# SCH_Lightbar-Sym_2024-08-25.net
KiCad netlist of a schematic drawn in EasyEDA
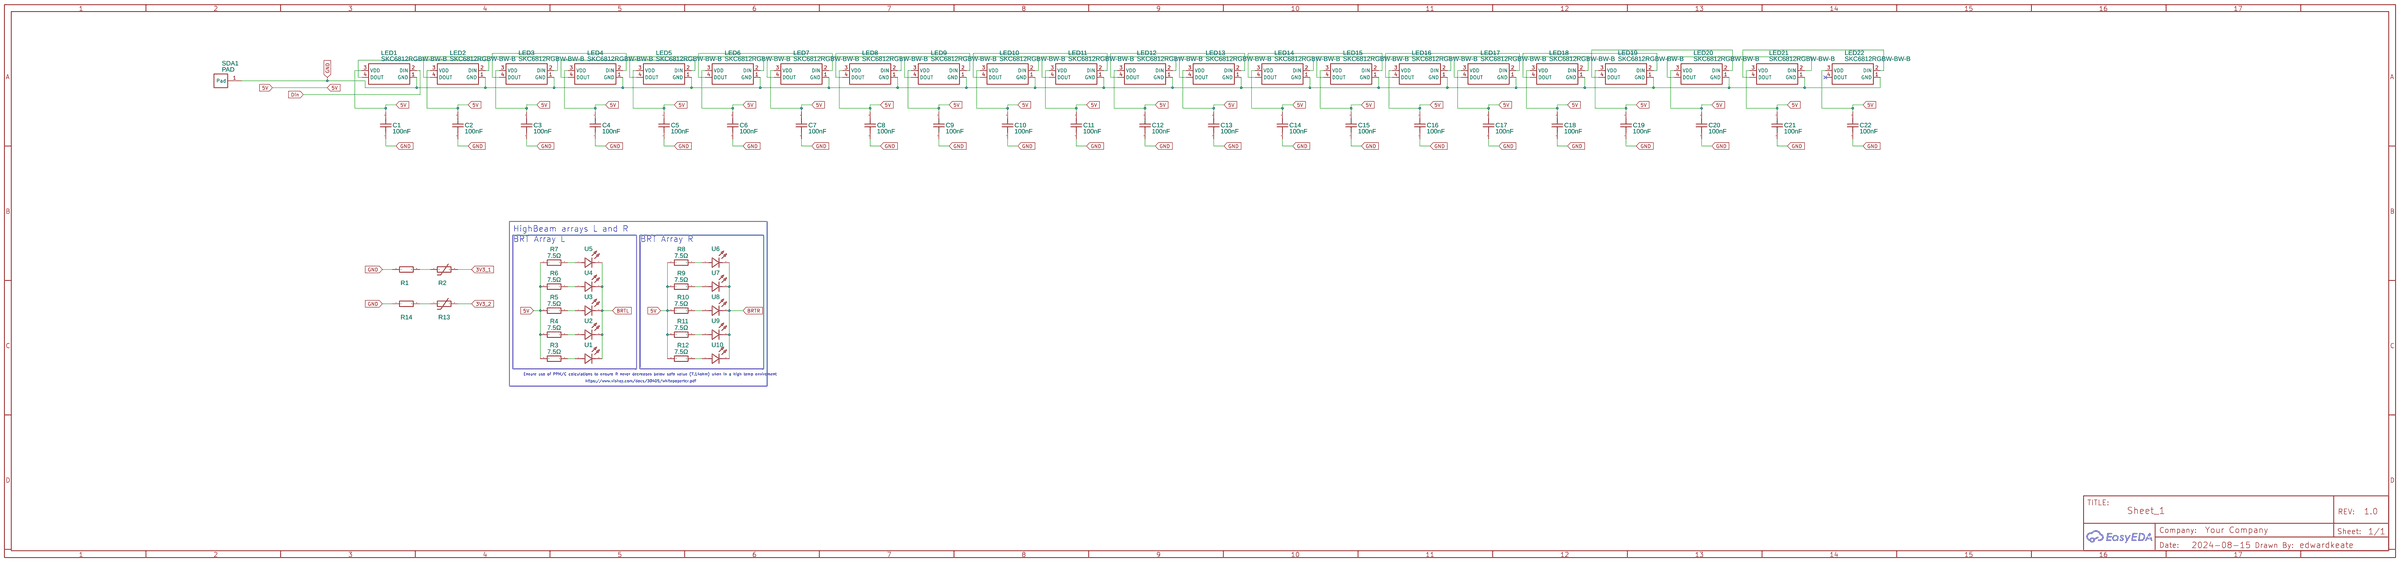
[diagram p0: schematic sheet]

(export (version "E")
  (design (tool "Eeschema 10.0.6"))
  (components
    (comp (ref "C1")
      (value "100nF")
      (fields
        (field (name "Manufacturer Part") "CC0402KRX7R6BB104")
        (field (name "Manufacturer") "YAGEO(国巨)")
      )
      (libsource (lib "") (part "CC0402KRX7R6BB104"))
    )
    (comp (ref "C2")
      (value "100nF")
      (fields
        (field (name "Manufacturer Part") "CC0402KRX7R6BB104")
        (field (name "Manufacturer") "YAGEO(国巨)")
      )
      (libsource (lib "") (part "CC0402KRX7R6BB104"))
    )
    (comp (ref "C3")
      (value "100nF")
      (fields
        (field (name "Manufacturer Part") "CC0402KRX7R6BB104")
        (field (name "Manufacturer") "YAGEO(国巨)")
      )
      (libsource (lib "") (part "CC0402KRX7R6BB104"))
    )
    (comp (ref "C4")
      (value "100nF")
      (fields
        (field (name "Manufacturer Part") "CC0402KRX7R6BB104")
        (field (name "Manufacturer") "YAGEO(国巨)")
      )
      (libsource (lib "") (part "CC0402KRX7R6BB104"))
    )
    (comp (ref "C5")
      (value "100nF")
      (fields
        (field (name "Manufacturer Part") "CC0402KRX7R6BB104")
        (field (name "Manufacturer") "YAGEO(国巨)")
      )
      (libsource (lib "") (part "CC0402KRX7R6BB104"))
    )
    (comp (ref "C6")
      (value "100nF")
      (fields
        (field (name "Manufacturer Part") "CC0402KRX7R6BB104")
        (field (name "Manufacturer") "YAGEO(国巨)")
      )
      (libsource (lib "") (part "CC0402KRX7R6BB104"))
    )
    (comp (ref "C7")
      (value "100nF")
      (fields
        (field (name "Manufacturer Part") "CC0402KRX7R6BB104")
        (field (name "Manufacturer") "YAGEO(国巨)")
      )
      (libsource (lib "") (part "CC0402KRX7R6BB104"))
    )
    (comp (ref "C8")
      (value "100nF")
      (fields
        (field (name "Manufacturer Part") "CC0402KRX7R6BB104")
        (field (name "Manufacturer") "YAGEO(国巨)")
      )
      (libsource (lib "") (part "CC0402KRX7R6BB104"))
    )
    (comp (ref "C9")
      (value "100nF")
      (fields
        (field (name "Manufacturer Part") "CC0402KRX7R6BB104")
        (field (name "Manufacturer") "YAGEO(国巨)")
      )
      (libsource (lib "") (part "CC0402KRX7R6BB104"))
    )
    (comp (ref "C10")
      (value "100nF")
      (fields
        (field (name "Manufacturer Part") "CC0402KRX7R6BB104")
        (field (name "Manufacturer") "YAGEO(国巨)")
      )
      (libsource (lib "") (part "CC0402KRX7R6BB104"))
    )
    (comp (ref "C11")
      (value "100nF")
      (fields
        (field (name "Manufacturer Part") "CC0402KRX7R6BB104")
        (field (name "Manufacturer") "YAGEO(国巨)")
      )
      (libsource (lib "") (part "CC0402KRX7R6BB104"))
    )
    (comp (ref "C12")
      (value "100nF")
      (fields
        (field (name "Manufacturer Part") "CC0402KRX7R6BB104")
        (field (name "Manufacturer") "YAGEO(国巨)")
      )
      (libsource (lib "") (part "CC0402KRX7R6BB104"))
    )
    (comp (ref "C13")
      (value "100nF")
      (fields
        (field (name "Manufacturer Part") "CC0402KRX7R6BB104")
        (field (name "Manufacturer") "YAGEO(国巨)")
      )
      (libsource (lib "") (part "CC0402KRX7R6BB104"))
    )
    (comp (ref "C14")
      (value "100nF")
      (fields
        (field (name "Manufacturer Part") "CC0402KRX7R6BB104")
        (field (name "Manufacturer") "YAGEO(国巨)")
      )
      (libsource (lib "") (part "CC0402KRX7R6BB104"))
    )
    (comp (ref "C15")
      (value "100nF")
      (fields
        (field (name "Manufacturer Part") "CC0402KRX7R6BB104")
        (field (name "Manufacturer") "YAGEO(国巨)")
      )
      (libsource (lib "") (part "CC0402KRX7R6BB104"))
    )
    (comp (ref "C16")
      (value "100nF")
      (fields
        (field (name "Manufacturer Part") "CC0402KRX7R6BB104")
        (field (name "Manufacturer") "YAGEO(国巨)")
      )
      (libsource (lib "") (part "CC0402KRX7R6BB104"))
    )
    (comp (ref "C17")
      (value "100nF")
      (fields
        (field (name "Manufacturer Part") "CC0402KRX7R6BB104")
        (field (name "Manufacturer") "YAGEO(国巨)")
      )
      (libsource (lib "") (part "CC0402KRX7R6BB104"))
    )
    (comp (ref "C18")
      (value "100nF")
      (fields
        (field (name "Manufacturer Part") "CC0402KRX7R6BB104")
        (field (name "Manufacturer") "YAGEO(国巨)")
      )
      (libsource (lib "") (part "CC0402KRX7R6BB104"))
    )
    (comp (ref "C19")
      (value "100nF")
      (fields
        (field (name "Manufacturer Part") "CC0402KRX7R6BB104")
        (field (name "Manufacturer") "YAGEO(国巨)")
      )
      (libsource (lib "") (part "CC0402KRX7R6BB104"))
    )
    (comp (ref "C20")
      (value "100nF")
      (fields
        (field (name "Manufacturer Part") "CC0402KRX7R6BB104")
        (field (name "Manufacturer") "YAGEO(国巨)")
      )
      (libsource (lib "") (part "CC0402KRX7R6BB104"))
    )
    (comp (ref "C21")
      (value "100nF")
      (fields
        (field (name "Manufacturer Part") "CC0402KRX7R6BB104")
        (field (name "Manufacturer") "YAGEO(国巨)")
      )
      (libsource (lib "") (part "CC0402KRX7R6BB104"))
    )
    (comp (ref "C22")
      (value "100nF")
      (fields
        (field (name "Manufacturer Part") "CC0402KRX7R6BB104")
        (field (name "Manufacturer") "YAGEO(国巨)")
      )
      (libsource (lib "") (part "CC0402KRX7R6BB104"))
    )
    (comp (ref "LED1")
      (value "SKC6812RGBW-BW-B")
      (fields (field (name "Manufacturer") "欧思科光电"))
      (libsource (lib "") (part "SKC6812RGBW-BW-B"))
    )
    (comp (ref "LED2")
      (value "SKC6812RGBW-BW-B")
      (fields (field (name "Manufacturer") "欧思科光电"))
      (libsource (lib "") (part "SKC6812RGBW-BW-B"))
    )
    (comp (ref "LED3")
      (value "SKC6812RGBW-BW-B")
      (fields (field (name "Manufacturer") "欧思科光电"))
      (libsource (lib "") (part "SKC6812RGBW-BW-B"))
    )
    (comp (ref "LED4")
      (value "SKC6812RGBW-BW-B")
      (fields (field (name "Manufacturer") "欧思科光电"))
      (libsource (lib "") (part "SKC6812RGBW-BW-B"))
    )
    (comp (ref "LED5")
      (value "SKC6812RGBW-BW-B")
      (fields (field (name "Manufacturer") "欧思科光电"))
      (libsource (lib "") (part "SKC6812RGBW-BW-B"))
    )
    (comp (ref "LED6")
      (value "SKC6812RGBW-BW-B")
      (fields (field (name "Manufacturer") "欧思科光电"))
      (libsource (lib "") (part "SKC6812RGBW-BW-B"))
    )
    (comp (ref "LED7")
      (value "SKC6812RGBW-BW-B")
      (fields (field (name "Manufacturer") "欧思科光电"))
      (libsource (lib "") (part "SKC6812RGBW-BW-B"))
    )
    (comp (ref "LED8")
      (value "SKC6812RGBW-BW-B")
      (fields (field (name "Manufacturer") "欧思科光电"))
      (libsource (lib "") (part "SKC6812RGBW-BW-B"))
    )
    (comp (ref "LED9")
      (value "SKC6812RGBW-BW-B")
      (fields (field (name "Manufacturer") "欧思科光电"))
      (libsource (lib "") (part "SKC6812RGBW-BW-B"))
    )
    (comp (ref "LED10")
      (value "SKC6812RGBW-BW-B")
      (fields (field (name "Manufacturer") "欧思科光电"))
      (libsource (lib "") (part "SKC6812RGBW-BW-B"))
    )
    (comp (ref "LED11")
      (value "SKC6812RGBW-BW-B")
      (fields (field (name "Manufacturer") "欧思科光电"))
      (libsource (lib "") (part "SKC6812RGBW-BW-B"))
    )
    (comp (ref "LED12")
      (value "SKC6812RGBW-BW-B")
      (fields (field (name "Manufacturer") "欧思科光电"))
      (libsource (lib "") (part "SKC6812RGBW-BW-B"))
    )
    (comp (ref "LED13")
      (value "SKC6812RGBW-BW-B")
      (fields (field (name "Manufacturer") "欧思科光电"))
      (libsource (lib "") (part "SKC6812RGBW-BW-B"))
    )
    (comp (ref "LED14")
      (value "SKC6812RGBW-BW-B")
      (fields (field (name "Manufacturer") "欧思科光电"))
      (libsource (lib "") (part "SKC6812RGBW-BW-B"))
    )
    (comp (ref "LED15")
      (value "SKC6812RGBW-BW-B")
      (fields (field (name "Manufacturer") "欧思科光电"))
      (libsource (lib "") (part "SKC6812RGBW-BW-B"))
    )
    (comp (ref "LED16")
      (value "SKC6812RGBW-BW-B")
      (fields (field (name "Manufacturer") "欧思科光电"))
      (libsource (lib "") (part "SKC6812RGBW-BW-B"))
    )
    (comp (ref "LED17")
      (value "SKC6812RGBW-BW-B")
      (fields (field (name "Manufacturer") "欧思科光电"))
      (libsource (lib "") (part "SKC6812RGBW-BW-B"))
    )
    (comp (ref "LED18")
      (value "SKC6812RGBW-BW-B")
      (fields (field (name "Manufacturer") "欧思科光电"))
      (libsource (lib "") (part "SKC6812RGBW-BW-B"))
    )
    (comp (ref "LED19")
      (value "SKC6812RGBW-BW-B")
      (fields (field (name "Manufacturer") "欧思科光电"))
      (libsource (lib "") (part "SKC6812RGBW-BW-B"))
    )
    (comp (ref "LED20")
      (value "SKC6812RGBW-BW-B")
      (fields (field (name "Manufacturer") "欧思科光电"))
      (libsource (lib "") (part "SKC6812RGBW-BW-B"))
    )
    (comp (ref "LED21")
      (value "SKC6812RGBW-BW-B")
      (fields (field (name "Manufacturer") "欧思科光电"))
      (libsource (lib "") (part "SKC6812RGBW-BW-B"))
    )
    (comp (ref "LED22")
      (value "SKC6812RGBW-BW-B")
      (fields (field (name "Manufacturer") "欧思科光电"))
      (libsource (lib "") (part "SKC6812RGBW-BW-B"))
    )
    (comp (ref "R1")
      (value "100kΩ")
      (fields
        (field (name "Manufacturer Part") "0603WAF1003T5E")
        (field (name "Manufacturer") "UNI-ROYAL(厚声)")
      )
      (libsource (lib "") (part "0603WAF1003T5E"))
    )
    (comp (ref "R2")
      (value "SDNT1608X104F3950FTF")
      (fields (field (name "Manufacturer") "Sunlord(顺络)"))
      (libsource (lib "") (part "SDNT1608X104F3950FTF"))
    )
    (comp (ref "R3")
      (value "7.5Ω")
      (fields
        (field (name "Manufacturer Part") "25121WF750KT4E")
        (field (name "Manufacturer") "UNI-ROYAL(厚声)")
      )
      (libsource (lib "") (part "25121WF750KT4E"))
    )
    (comp (ref "R4")
      (value "7.5Ω")
      (fields
        (field (name "Manufacturer Part") "25121WF750KT4E")
        (field (name "Manufacturer") "UNI-ROYAL(厚声)")
      )
      (libsource (lib "") (part "25121WF750KT4E"))
    )
    (comp (ref "R5")
      (value "7.5Ω")
      (fields
        (field (name "Manufacturer Part") "25121WF750KT4E")
        (field (name "Manufacturer") "UNI-ROYAL(厚声)")
      )
      (libsource (lib "") (part "25121WF750KT4E"))
    )
    (comp (ref "R6")
      (value "7.5Ω")
      (fields
        (field (name "Manufacturer Part") "25121WF750KT4E")
        (field (name "Manufacturer") "UNI-ROYAL(厚声)")
      )
      (libsource (lib "") (part "25121WF750KT4E"))
    )
    (comp (ref "R7")
      (value "7.5Ω")
      (fields
        (field (name "Manufacturer Part") "25121WF750KT4E")
        (field (name "Manufacturer") "UNI-ROYAL(厚声)")
      )
      (libsource (lib "") (part "25121WF750KT4E"))
    )
    (comp (ref "R8")
      (value "7.5Ω")
      (fields
        (field (name "Manufacturer Part") "25121WF750KT4E")
        (field (name "Manufacturer") "UNI-ROYAL(厚声)")
      )
      (libsource (lib "") (part "25121WF750KT4E"))
    )
    (comp (ref "R9")
      (value "7.5Ω")
      (fields
        (field (name "Manufacturer Part") "25121WF750KT4E")
        (field (name "Manufacturer") "UNI-ROYAL(厚声)")
      )
      (libsource (lib "") (part "25121WF750KT4E"))
    )
    (comp (ref "R10")
      (value "7.5Ω")
      (fields
        (field (name "Manufacturer Part") "25121WF750KT4E")
        (field (name "Manufacturer") "UNI-ROYAL(厚声)")
      )
      (libsource (lib "") (part "25121WF750KT4E"))
    )
    (comp (ref "R11")
      (value "7.5Ω")
      (fields
        (field (name "Manufacturer Part") "25121WF750KT4E")
        (field (name "Manufacturer") "UNI-ROYAL(厚声)")
      )
      (libsource (lib "") (part "25121WF750KT4E"))
    )
    (comp (ref "R12")
      (value "7.5Ω")
      (fields
        (field (name "Manufacturer Part") "25121WF750KT4E")
        (field (name "Manufacturer") "UNI-ROYAL(厚声)")
      )
      (libsource (lib "") (part "25121WF750KT4E"))
    )
    (comp (ref "R13")
      (value "SDNT1608X104F3950FTF")
      (fields (field (name "Manufacturer") "Sunlord(顺络)"))
      (libsource (lib "") (part "SDNT1608X104F3950FTF"))
    )
    (comp (ref "R14")
      (value "100kΩ")
      (fields
        (field (name "Manufacturer Part") "0603WAF1003T5E")
        (field (name "Manufacturer") "UNI-ROYAL(厚声)")
      )
      (libsource (lib "") (part "0603WAF1003T5E"))
    )
    (comp (ref "SDA1") (value "PAD") (libsource (lib "") (part "PAD")))
    (comp (ref "U1")
      (value "JNJ-LTJH0111W60/26MIL/8000-9000K")
      (fields
        (field (name "Manufacturer Part") "JNJ-LTJH0111W60/26mil/8000-9000K")
        (field (name "Manufacturer") "JNJ OPTOELECTRONICS(强生光电)")
      )
      (libsource (lib "") (part "JNJ-LTJH0111W60/26MIL/8000-9000K"))
    )
    (comp (ref "U2")
      (value "JNJ-LTJH0111W60/26MIL/8000-9000K")
      (fields
        (field (name "Manufacturer Part") "JNJ-LTJH0111W60/26mil/8000-9000K")
        (field (name "Manufacturer") "JNJ OPTOELECTRONICS(强生光电)")
      )
      (libsource (lib "") (part "JNJ-LTJH0111W60/26MIL/8000-9000K"))
    )
    (comp (ref "U3")
      (value "JNJ-LTJH0111W60/26MIL/8000-9000K")
      (fields
        (field (name "Manufacturer Part") "JNJ-LTJH0111W60/26mil/8000-9000K")
        (field (name "Manufacturer") "JNJ OPTOELECTRONICS(强生光电)")
      )
      (libsource (lib "") (part "JNJ-LTJH0111W60/26MIL/8000-9000K"))
    )
    (comp (ref "U4")
      (value "JNJ-LTJH0111W60/26MIL/8000-9000K")
      (fields
        (field (name "Manufacturer Part") "JNJ-LTJH0111W60/26mil/8000-9000K")
        (field (name "Manufacturer") "JNJ OPTOELECTRONICS(强生光电)")
      )
      (libsource (lib "") (part "JNJ-LTJH0111W60/26MIL/8000-9000K"))
    )
    (comp (ref "U5")
      (value "JNJ-LTJH0111W60/26MIL/8000-9000K")
      (fields
        (field (name "Manufacturer Part") "JNJ-LTJH0111W60/26mil/8000-9000K")
        (field (name "Manufacturer") "JNJ OPTOELECTRONICS(强生光电)")
      )
      (libsource (lib "") (part "JNJ-LTJH0111W60/26MIL/8000-9000K"))
    )
    (comp (ref "U6")
      (value "JNJ-LTJH0111W60/26MIL/8000-9000K")
      (fields
        (field (name "Manufacturer Part") "JNJ-LTJH0111W60/26mil/8000-9000K")
        (field (name "Manufacturer") "JNJ OPTOELECTRONICS(强生光电)")
      )
      (libsource (lib "") (part "JNJ-LTJH0111W60/26MIL/8000-9000K"))
    )
    (comp (ref "U7")
      (value "JNJ-LTJH0111W60/26MIL/8000-9000K")
      (fields
        (field (name "Manufacturer Part") "JNJ-LTJH0111W60/26mil/8000-9000K")
        (field (name "Manufacturer") "JNJ OPTOELECTRONICS(强生光电)")
      )
      (libsource (lib "") (part "JNJ-LTJH0111W60/26MIL/8000-9000K"))
    )
    (comp (ref "U8")
      (value "JNJ-LTJH0111W60/26MIL/8000-9000K")
      (fields
        (field (name "Manufacturer Part") "JNJ-LTJH0111W60/26mil/8000-9000K")
        (field (name "Manufacturer") "JNJ OPTOELECTRONICS(强生光电)")
      )
      (libsource (lib "") (part "JNJ-LTJH0111W60/26MIL/8000-9000K"))
    )
    (comp (ref "U9")
      (value "JNJ-LTJH0111W60/26MIL/8000-9000K")
      (fields
        (field (name "Manufacturer Part") "JNJ-LTJH0111W60/26mil/8000-9000K")
        (field (name "Manufacturer") "JNJ OPTOELECTRONICS(强生光电)")
      )
      (libsource (lib "") (part "JNJ-LTJH0111W60/26MIL/8000-9000K"))
    )
    (comp (ref "U10")
      (value "JNJ-LTJH0111W60/26MIL/8000-9000K")
      (fields
        (field (name "Manufacturer Part") "JNJ-LTJH0111W60/26mil/8000-9000K")
        (field (name "Manufacturer") "JNJ OPTOELECTRONICS(强生光电)")
      )
      (libsource (lib "") (part "JNJ-LTJH0111W60/26MIL/8000-9000K"))
    )
  )
  (nets
    (net (code "1") (name "3V3_1") (class "Default")
      (node (ref "R2") (pin "2") (pinfunction "2_2") (pintype "unspecified"))
    )
    (net (code "2") (name "3V3_2") (class "Default")
      (node (ref "R13") (pin "2") (pinfunction "2_2") (pintype "unspecified"))
    )
    (net (code "3") (name "5V") (class "Default")
      (node (ref "C1") (pin "2") (pinfunction "2_2") (pintype "unspecified"))
      (node (ref "C10") (pin "2") (pinfunction "2_2") (pintype "unspecified"))
      (node (ref "C11") (pin "2") (pinfunction "2_2") (pintype "unspecified"))
      (node (ref "C12") (pin "2") (pinfunction "2_2") (pintype "unspecified"))
      (node (ref "C13") (pin "2") (pinfunction "2_2") (pintype "unspecified"))
      (node (ref "C14") (pin "2") (pinfunction "2_2") (pintype "unspecified"))
      (node (ref "C15") (pin "2") (pinfunction "2_2") (pintype "unspecified"))
      (node (ref "C16") (pin "2") (pinfunction "2_2") (pintype "unspecified"))
      (node (ref "C17") (pin "2") (pinfunction "2_2") (pintype "unspecified"))
      (node (ref "C18") (pin "2") (pinfunction "2_2") (pintype "unspecified"))
      (node (ref "C19") (pin "2") (pinfunction "2_2") (pintype "unspecified"))
      (node (ref "C2") (pin "2") (pinfunction "2_2") (pintype "unspecified"))
      (node (ref "C20") (pin "2") (pinfunction "2_2") (pintype "unspecified"))
      (node (ref "C21") (pin "2") (pinfunction "2_2") (pintype "unspecified"))
      (node (ref "C22") (pin "2") (pinfunction "2_2") (pintype "unspecified"))
      (node (ref "C3") (pin "2") (pinfunction "2_2") (pintype "unspecified"))
      (node (ref "C4") (pin "2") (pinfunction "2_2") (pintype "unspecified"))
      (node (ref "C5") (pin "2") (pinfunction "2_2") (pintype "unspecified"))
      (node (ref "C6") (pin "2") (pinfunction "2_2") (pintype "unspecified"))
      (node (ref "C7") (pin "2") (pinfunction "2_2") (pintype "unspecified"))
      (node (ref "C8") (pin "2") (pinfunction "2_2") (pintype "unspecified"))
      (node (ref "C9") (pin "2") (pinfunction "2_2") (pintype "unspecified"))
      (node (ref "LED1") (pin "3") (pinfunction "VDD_3") (pintype "unspecified"))
      (node (ref "LED10") (pin "3") (pinfunction "VDD_3") (pintype "unspecified"))
      (node (ref "LED11") (pin "3") (pinfunction "VDD_3") (pintype "unspecified"))
      (node (ref "LED12") (pin "3") (pinfunction "VDD_3") (pintype "unspecified"))
      (node (ref "LED13") (pin "3") (pinfunction "VDD_3") (pintype "unspecified"))
      (node (ref "LED14") (pin "3") (pinfunction "VDD_3") (pintype "unspecified"))
      (node (ref "LED15") (pin "3") (pinfunction "VDD_3") (pintype "unspecified"))
      (node (ref "LED16") (pin "3") (pinfunction "VDD_3") (pintype "unspecified"))
      (node (ref "LED17") (pin "3") (pinfunction "VDD_3") (pintype "unspecified"))
      (node (ref "LED18") (pin "3") (pinfunction "VDD_3") (pintype "unspecified"))
      (node (ref "LED19") (pin "3") (pinfunction "VDD_3") (pintype "unspecified"))
      (node (ref "LED2") (pin "3") (pinfunction "VDD_3") (pintype "unspecified"))
      (node (ref "LED20") (pin "3") (pinfunction "VDD_3") (pintype "unspecified"))
      (node (ref "LED21") (pin "3") (pinfunction "VDD_3") (pintype "unspecified"))
      (node (ref "LED22") (pin "3") (pinfunction "VDD_3") (pintype "unspecified"))
      (node (ref "LED3") (pin "3") (pinfunction "VDD_3") (pintype "unspecified"))
      (node (ref "LED4") (pin "3") (pinfunction "VDD_3") (pintype "unspecified"))
      (node (ref "LED5") (pin "3") (pinfunction "VDD_3") (pintype "unspecified"))
      (node (ref "LED6") (pin "3") (pinfunction "VDD_3") (pintype "unspecified"))
      (node (ref "LED7") (pin "3") (pinfunction "VDD_3") (pintype "unspecified"))
      (node (ref "LED8") (pin "3") (pinfunction "VDD_3") (pintype "unspecified"))
      (node (ref "LED9") (pin "3") (pinfunction "VDD_3") (pintype "unspecified"))
      (node (ref "R10") (pin "1") (pinfunction "1_1") (pintype "input"))
      (node (ref "R11") (pin "1") (pinfunction "1_1") (pintype "input"))
      (node (ref "R12") (pin "1") (pinfunction "1_1") (pintype "input"))
      (node (ref "R3") (pin "1") (pinfunction "1_1") (pintype "input"))
      (node (ref "R4") (pin "1") (pinfunction "1_1") (pintype "input"))
      (node (ref "R5") (pin "1") (pinfunction "1_1") (pintype "input"))
      (node (ref "R6") (pin "1") (pinfunction "1_1") (pintype "input"))
      (node (ref "R7") (pin "1") (pinfunction "1_1") (pintype "input"))
      (node (ref "R8") (pin "1") (pinfunction "1_1") (pintype "input"))
      (node (ref "R9") (pin "1") (pinfunction "1_1") (pintype "input"))
    )
    (net (code "4") (name "BRTL") (class "Default")
      (node (ref "U1") (pin "2") (pinfunction "K_2") (pintype "unspecified"))
      (node (ref "U2") (pin "2") (pinfunction "K_2") (pintype "unspecified"))
      (node (ref "U3") (pin "2") (pinfunction "K_2") (pintype "unspecified"))
      (node (ref "U4") (pin "2") (pinfunction "K_2") (pintype "unspecified"))
      (node (ref "U5") (pin "2") (pinfunction "K_2") (pintype "unspecified"))
    )
    (net (code "5") (name "BRTR") (class "Default")
      (node (ref "U10") (pin "2") (pinfunction "K_2") (pintype "unspecified"))
      (node (ref "U6") (pin "2") (pinfunction "K_2") (pintype "unspecified"))
      (node (ref "U7") (pin "2") (pinfunction "K_2") (pintype "unspecified"))
      (node (ref "U8") (pin "2") (pinfunction "K_2") (pintype "unspecified"))
      (node (ref "U9") (pin "2") (pinfunction "K_2") (pintype "unspecified"))
    )
    (net (code "6") (name "Din") (class "Default")
      (node (ref "LED1") (pin "2") (pinfunction "DIN_2") (pintype "unspecified"))
    )
    (net (code "7") (name "GND") (class "Default")
      (node (ref "C1") (pin "1") (pinfunction "1_1") (pintype "unspecified"))
      (node (ref "C10") (pin "1") (pinfunction "1_1") (pintype "unspecified"))
      (node (ref "C11") (pin "1") (pinfunction "1_1") (pintype "unspecified"))
      (node (ref "C12") (pin "1") (pinfunction "1_1") (pintype "unspecified"))
      (node (ref "C13") (pin "1") (pinfunction "1_1") (pintype "unspecified"))
      (node (ref "C14") (pin "1") (pinfunction "1_1") (pintype "unspecified"))
      (node (ref "C15") (pin "1") (pinfunction "1_1") (pintype "unspecified"))
      (node (ref "C16") (pin "1") (pinfunction "1_1") (pintype "unspecified"))
      (node (ref "C17") (pin "1") (pinfunction "1_1") (pintype "unspecified"))
      (node (ref "C18") (pin "1") (pinfunction "1_1") (pintype "unspecified"))
      (node (ref "C19") (pin "1") (pinfunction "1_1") (pintype "unspecified"))
      (node (ref "C2") (pin "1") (pinfunction "1_1") (pintype "unspecified"))
      (node (ref "C20") (pin "1") (pinfunction "1_1") (pintype "unspecified"))
      (node (ref "C21") (pin "1") (pinfunction "1_1") (pintype "unspecified"))
      (node (ref "C22") (pin "1") (pinfunction "1_1") (pintype "unspecified"))
      (node (ref "C3") (pin "1") (pinfunction "1_1") (pintype "unspecified"))
      (node (ref "C4") (pin "1") (pinfunction "1_1") (pintype "unspecified"))
      (node (ref "C5") (pin "1") (pinfunction "1_1") (pintype "unspecified"))
      (node (ref "C6") (pin "1") (pinfunction "1_1") (pintype "unspecified"))
      (node (ref "C7") (pin "1") (pinfunction "1_1") (pintype "unspecified"))
      (node (ref "C8") (pin "1") (pinfunction "1_1") (pintype "unspecified"))
      (node (ref "C9") (pin "1") (pinfunction "1_1") (pintype "unspecified"))
      (node (ref "LED1") (pin "1") (pinfunction "GND_1") (pintype "unspecified"))
      (node (ref "LED10") (pin "1") (pinfunction "GND_1") (pintype "unspecified"))
      (node (ref "LED11") (pin "1") (pinfunction "GND_1") (pintype "unspecified"))
      (node (ref "LED12") (pin "1") (pinfunction "GND_1") (pintype "unspecified"))
      (node (ref "LED13") (pin "1") (pinfunction "GND_1") (pintype "unspecified"))
      (node (ref "LED14") (pin "1") (pinfunction "GND_1") (pintype "unspecified"))
      (node (ref "LED15") (pin "1") (pinfunction "GND_1") (pintype "unspecified"))
      (node (ref "LED16") (pin "1") (pinfunction "GND_1") (pintype "unspecified"))
      (node (ref "LED17") (pin "1") (pinfunction "GND_1") (pintype "unspecified"))
      (node (ref "LED18") (pin "1") (pinfunction "GND_1") (pintype "unspecified"))
      (node (ref "LED19") (pin "1") (pinfunction "GND_1") (pintype "unspecified"))
      (node (ref "LED2") (pin "1") (pinfunction "GND_1") (pintype "unspecified"))
      (node (ref "LED20") (pin "1") (pinfunction "GND_1") (pintype "unspecified"))
      (node (ref "LED21") (pin "1") (pinfunction "GND_1") (pintype "unspecified"))
      (node (ref "LED22") (pin "1") (pinfunction "GND_1") (pintype "unspecified"))
      (node (ref "LED3") (pin "1") (pinfunction "GND_1") (pintype "unspecified"))
      (node (ref "LED4") (pin "1") (pinfunction "GND_1") (pintype "unspecified"))
      (node (ref "LED5") (pin "1") (pinfunction "GND_1") (pintype "unspecified"))
      (node (ref "LED6") (pin "1") (pinfunction "GND_1") (pintype "unspecified"))
      (node (ref "LED7") (pin "1") (pinfunction "GND_1") (pintype "unspecified"))
      (node (ref "LED8") (pin "1") (pinfunction "GND_1") (pintype "unspecified"))
      (node (ref "LED9") (pin "1") (pinfunction "GND_1") (pintype "unspecified"))
      (node (ref "R1") (pin "1") (pinfunction "1_1") (pintype "input"))
      (node (ref "R14") (pin "1") (pinfunction "1_1") (pintype "input"))
      (node (ref "SDA1") (pin "1") (pinfunction "Pad_1") (pintype "unspecified"))
    )
    (net (code "8") (name "Net-(LED1-DOUT)") (class "Default")
      (node (ref "LED1") (pin "4") (pinfunction "DOUT_4") (pintype "unspecified"))
      (node (ref "LED2") (pin "2") (pinfunction "DIN_2") (pintype "unspecified"))
    )
    (net (code "9") (name "Net-(LED2-DOUT)") (class "Default")
      (node (ref "LED2") (pin "4") (pinfunction "DOUT_4") (pintype "unspecified"))
      (node (ref "LED3") (pin "2") (pinfunction "DIN_2") (pintype "unspecified"))
    )
    (net (code "10") (name "Net-(LED3-DOUT)") (class "Default")
      (node (ref "LED3") (pin "4") (pinfunction "DOUT_4") (pintype "unspecified"))
      (node (ref "LED4") (pin "2") (pinfunction "DIN_2") (pintype "unspecified"))
    )
    (net (code "11") (name "Net-(LED4-DOUT)") (class "Default")
      (node (ref "LED4") (pin "4") (pinfunction "DOUT_4") (pintype "unspecified"))
      (node (ref "LED5") (pin "2") (pinfunction "DIN_2") (pintype "unspecified"))
    )
    (net (code "12") (name "Net-(LED5-DOUT)") (class "Default")
      (node (ref "LED5") (pin "4") (pinfunction "DOUT_4") (pintype "unspecified"))
      (node (ref "LED6") (pin "2") (pinfunction "DIN_2") (pintype "unspecified"))
    )
    (net (code "13") (name "Net-(LED6-DOUT)") (class "Default")
      (node (ref "LED6") (pin "4") (pinfunction "DOUT_4") (pintype "unspecified"))
      (node (ref "LED7") (pin "2") (pinfunction "DIN_2") (pintype "unspecified"))
    )
    (net (code "14") (name "Net-(LED7-DOUT)") (class "Default")
      (node (ref "LED7") (pin "4") (pinfunction "DOUT_4") (pintype "unspecified"))
      (node (ref "LED8") (pin "2") (pinfunction "DIN_2") (pintype "unspecified"))
    )
    (net (code "15") (name "Net-(LED8-DOUT)") (class "Default")
      (node (ref "LED8") (pin "4") (pinfunction "DOUT_4") (pintype "unspecified"))
      (node (ref "LED9") (pin "2") (pinfunction "DIN_2") (pintype "unspecified"))
    )
    (net (code "16") (name "Net-(LED10-DIN)") (class "Default")
      (node (ref "LED10") (pin "2") (pinfunction "DIN_2") (pintype "unspecified"))
      (node (ref "LED9") (pin "4") (pinfunction "DOUT_4") (pintype "unspecified"))
    )
    (net (code "17") (name "Net-(LED10-DOUT)") (class "Default")
      (node (ref "LED10") (pin "4") (pinfunction "DOUT_4") (pintype "unspecified"))
      (node (ref "LED11") (pin "2") (pinfunction "DIN_2") (pintype "unspecified"))
    )
    (net (code "18") (name "Net-(LED11-DOUT)") (class "Default")
      (node (ref "LED11") (pin "4") (pinfunction "DOUT_4") (pintype "unspecified"))
      (node (ref "LED12") (pin "2") (pinfunction "DIN_2") (pintype "unspecified"))
    )
    (net (code "19") (name "Net-(LED12-DOUT)") (class "Default")
      (node (ref "LED12") (pin "4") (pinfunction "DOUT_4") (pintype "unspecified"))
      (node (ref "LED13") (pin "2") (pinfunction "DIN_2") (pintype "unspecified"))
    )
    (net (code "20") (name "Net-(LED13-DOUT)") (class "Default")
      (node (ref "LED13") (pin "4") (pinfunction "DOUT_4") (pintype "unspecified"))
      (node (ref "LED14") (pin "2") (pinfunction "DIN_2") (pintype "unspecified"))
    )
    (net (code "21") (name "Net-(LED14-DOUT)") (class "Default")
      (node (ref "LED14") (pin "4") (pinfunction "DOUT_4") (pintype "unspecified"))
      (node (ref "LED15") (pin "2") (pinfunction "DIN_2") (pintype "unspecified"))
    )
    (net (code "22") (name "Net-(LED15-DOUT)") (class "Default")
      (node (ref "LED15") (pin "4") (pinfunction "DOUT_4") (pintype "unspecified"))
      (node (ref "LED16") (pin "2") (pinfunction "DIN_2") (pintype "unspecified"))
    )
    (net (code "23") (name "Net-(LED16-DOUT)") (class "Default")
      (node (ref "LED16") (pin "4") (pinfunction "DOUT_4") (pintype "unspecified"))
      (node (ref "LED17") (pin "2") (pinfunction "DIN_2") (pintype "unspecified"))
    )
    (net (code "24") (name "Net-(LED17-DOUT)") (class "Default")
      (node (ref "LED17") (pin "4") (pinfunction "DOUT_4") (pintype "unspecified"))
      (node (ref "LED18") (pin "2") (pinfunction "DIN_2") (pintype "unspecified"))
    )
    (net (code "25") (name "Net-(LED18-DOUT)") (class "Default")
      (node (ref "LED18") (pin "4") (pinfunction "DOUT_4") (pintype "unspecified"))
      (node (ref "LED19") (pin "2") (pinfunction "DIN_2") (pintype "unspecified"))
    )
    (net (code "26") (name "Net-(LED19-DOUT)") (class "Default")
      (node (ref "LED19") (pin "4") (pinfunction "DOUT_4") (pintype "unspecified"))
      (node (ref "LED20") (pin "2") (pinfunction "DIN_2") (pintype "unspecified"))
    )
    (net (code "27") (name "Net-(LED20-DOUT)") (class "Default")
      (node (ref "LED20") (pin "4") (pinfunction "DOUT_4") (pintype "unspecified"))
      (node (ref "LED21") (pin "2") (pinfunction "DIN_2") (pintype "unspecified"))
    )
    (net (code "28") (name "Net-(LED21-DOUT)") (class "Default")
      (node (ref "LED21") (pin "4") (pinfunction "DOUT_4") (pintype "unspecified"))
      (node (ref "LED22") (pin "2") (pinfunction "DIN_2") (pintype "unspecified"))
    )
    (net (code "29") (name "Net-(R1-Pad2)") (class "Default")
      (node (ref "R1") (pin "2") (pinfunction "2_2") (pintype "input"))
      (node (ref "R2") (pin "1") (pinfunction "1_1") (pintype "unspecified"))
    )
    (net (code "30") (name "Net-(R13-Pad1)") (class "Default")
      (node (ref "R13") (pin "1") (pinfunction "1_1") (pintype "unspecified"))
      (node (ref "R14") (pin "2") (pinfunction "2_2") (pintype "input"))
    )
    (net (code "31") (name "Net-(U1-A)") (class "Default")
      (node (ref "R3") (pin "2") (pinfunction "2_2") (pintype "input"))
      (node (ref "U1") (pin "1") (pinfunction "A_1") (pintype "unspecified"))
    )
    (net (code "32") (name "Net-(U2-A)") (class "Default")
      (node (ref "R4") (pin "2") (pinfunction "2_2") (pintype "input"))
      (node (ref "U2") (pin "1") (pinfunction "A_1") (pintype "unspecified"))
    )
    (net (code "33") (name "Net-(U3-A)") (class "Default")
      (node (ref "R5") (pin "2") (pinfunction "2_2") (pintype "input"))
      (node (ref "U3") (pin "1") (pinfunction "A_1") (pintype "unspecified"))
    )
    (net (code "34") (name "Net-(U4-A)") (class "Default")
      (node (ref "R6") (pin "2") (pinfunction "2_2") (pintype "input"))
      (node (ref "U4") (pin "1") (pinfunction "A_1") (pintype "unspecified"))
    )
    (net (code "35") (name "Net-(U5-A)") (class "Default")
      (node (ref "R7") (pin "2") (pinfunction "2_2") (pintype "input"))
      (node (ref "U5") (pin "1") (pinfunction "A_1") (pintype "unspecified"))
    )
    (net (code "36") (name "Net-(U6-A)") (class "Default")
      (node (ref "R8") (pin "2") (pinfunction "2_2") (pintype "input"))
      (node (ref "U6") (pin "1") (pinfunction "A_1") (pintype "unspecified"))
    )
    (net (code "37") (name "Net-(U7-A)") (class "Default")
      (node (ref "R9") (pin "2") (pinfunction "2_2") (pintype "input"))
      (node (ref "U7") (pin "1") (pinfunction "A_1") (pintype "unspecified"))
    )
    (net (code "38") (name "Net-(U8-A)") (class "Default")
      (node (ref "R10") (pin "2") (pinfunction "2_2") (pintype "input"))
      (node (ref "U8") (pin "1") (pinfunction "A_1") (pintype "unspecified"))
    )
    (net (code "39") (name "Net-(U9-A)") (class "Default")
      (node (ref "R11") (pin "2") (pinfunction "2_2") (pintype "input"))
      (node (ref "U9") (pin "1") (pinfunction "A_1") (pintype "unspecified"))
    )
    (net (code "40") (name "Net-(U10-A)") (class "Default")
      (node (ref "R12") (pin "2") (pinfunction "2_2") (pintype "input"))
      (node (ref "U10") (pin "1") (pinfunction "A_1") (pintype "unspecified"))
    )
    (net (code "41") (name "unconnected-(LED22-DOUT-Pad4)") (class "Default")
      (node (ref "LED22") (pin "4") (pinfunction "DOUT_4") (pintype "unspecified+no_connect"))
    )
  )
)
